# MAIN.net
KiCad netlist of a schematic drawn in Altium Designer
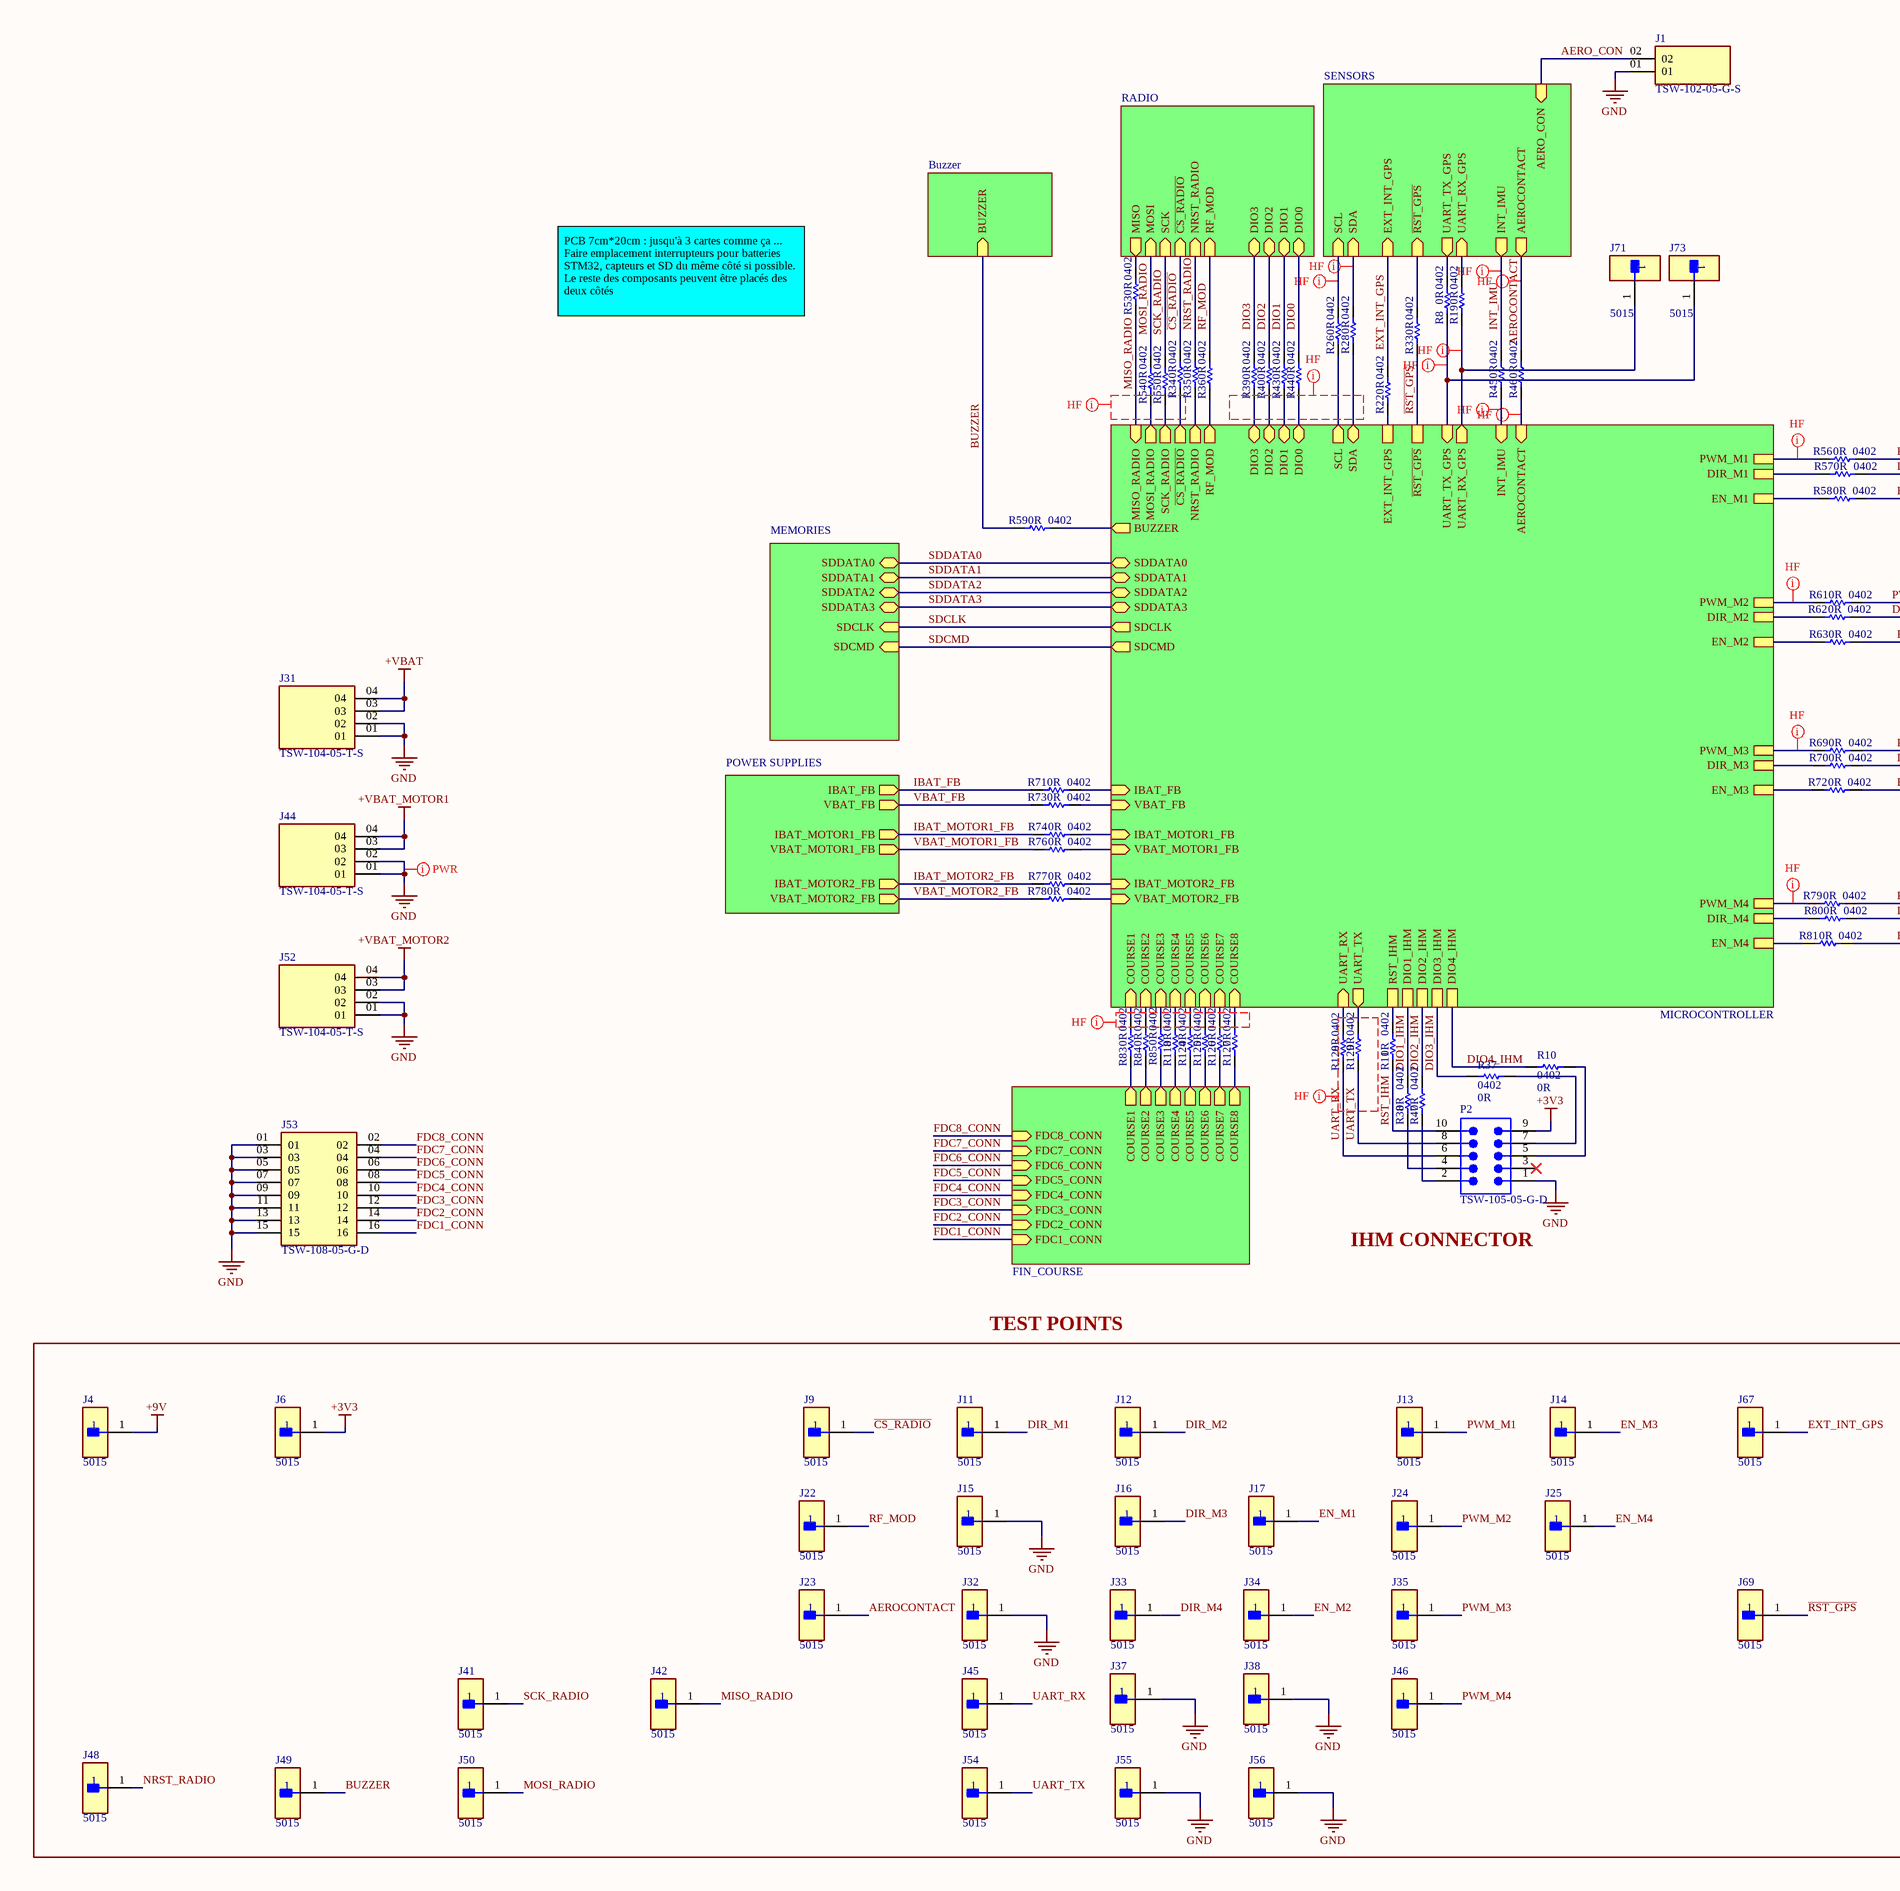
[diagram p0: MAIN.SchDoc, left]
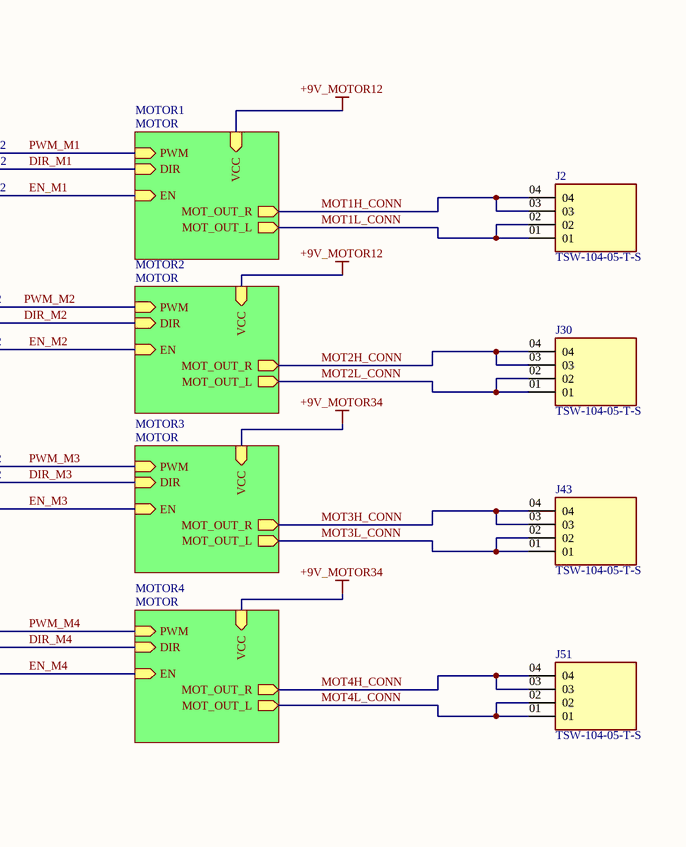
[diagram p1: MAIN.SchDoc, right]

(export (version "E")
  (design (tool "Eeschema 10.0.6"))
  (components
    (comp (ref "J1")
      (value "TSW-102-05-G-S")
      (footprint "TSW-102-05-G-S:SAMTEC_TSW-102-05-G-S")
      (fields (field (name "MF") "{'manufacturer': u'Samtec Inc.'}"))
      (libsource (lib "*") (part "TSW-102-05-G-S"))
    )
    (comp (ref "J2")
      (value "TSW-104-05-T-S")
      (footprint "TSW-104-05-T-S:SAMTEC_TSW-104-05-T-S")
      (fields (field (name "MF") "{'manufacturer': u'Samtec'}"))
      (libsource (lib "") (part "TSW-104-05-T-S_1"))
    )
    (comp (ref "J4")
      (value "5015")
      (footprint "FP-5015-MFG")
      (description "PC TEST POINT MINIATURE")
      (fields
        (field (name "MANUFACTURER") "keystone")
        (field (name "OCTOPART") "https://octopart.com/5015-keystone-3822")
      )
      (libsource (lib "Altium Content Vault") (part "dd45045ce8184df9e99e12baf3f412c"))
    )
    (comp (ref "J6")
      (value "5015")
      (footprint "FP-5015-MFG")
      (description "PC TEST POINT MINIATURE")
      (fields
        (field (name "MANUFACTURER") "keystone")
        (field (name "OCTOPART") "https://octopart.com/5015-keystone-3822")
      )
      (libsource (lib "Altium Content Vault") (part "dd45045ce8184df9e99e12baf3f412c"))
    )
    (comp (ref "J9")
      (value "5015")
      (footprint "FP-5015-MFG")
      (description "PC TEST POINT MINIATURE")
      (fields
        (field (name "MANUFACTURER") "keystone")
        (field (name "OCTOPART") "https://octopart.com/5015-keystone-3822")
      )
      (libsource (lib "Altium Content Vault") (part "dd45045ce8184df9e99e12baf3f412c"))
    )
    (comp (ref "J11")
      (value "5015")
      (footprint "FP-5015-MFG")
      (description "PC TEST POINT MINIATURE")
      (fields
        (field (name "MANUFACTURER") "keystone")
        (field (name "OCTOPART") "https://octopart.com/5015-keystone-3822")
      )
      (libsource (lib "Altium Content Vault") (part "dd45045ce8184df9e99e12baf3f412c"))
    )
    (comp (ref "J12")
      (value "5015")
      (footprint "FP-5015-MFG")
      (description "PC TEST POINT MINIATURE")
      (fields
        (field (name "MANUFACTURER") "keystone")
        (field (name "OCTOPART") "https://octopart.com/5015-keystone-3822")
      )
      (libsource (lib "Altium Content Vault") (part "dd45045ce8184df9e99e12baf3f412c"))
    )
    (comp (ref "J13")
      (value "5015")
      (footprint "FP-5015-MFG")
      (description "PC TEST POINT MINIATURE")
      (fields
        (field (name "MANUFACTURER") "keystone")
        (field (name "OCTOPART") "https://octopart.com/5015-keystone-3822")
      )
      (libsource (lib "Altium Content Vault") (part "dd45045ce8184df9e99e12baf3f412c"))
    )
    (comp (ref "J14")
      (value "5015")
      (footprint "FP-5015-MFG")
      (description "PC TEST POINT MINIATURE")
      (fields
        (field (name "MANUFACTURER") "keystone")
        (field (name "OCTOPART") "https://octopart.com/5015-keystone-3822")
      )
      (libsource (lib "Altium Content Vault") (part "dd45045ce8184df9e99e12baf3f412c"))
    )
    (comp (ref "J15")
      (value "5015")
      (footprint "FP-5015-MFG")
      (description "PC TEST POINT MINIATURE")
      (fields
        (field (name "MANUFACTURER") "keystone")
        (field (name "OCTOPART") "https://octopart.com/5015-keystone-3822")
      )
      (libsource (lib "Altium Content Vault") (part "dd45045ce8184df9e99e12baf3f412c"))
    )
    (comp (ref "J16")
      (value "5015")
      (footprint "FP-5015-MFG")
      (description "PC TEST POINT MINIATURE")
      (fields
        (field (name "MANUFACTURER") "keystone")
        (field (name "OCTOPART") "https://octopart.com/5015-keystone-3822")
      )
      (libsource (lib "Altium Content Vault") (part "dd45045ce8184df9e99e12baf3f412c"))
    )
    (comp (ref "J17")
      (value "5015")
      (footprint "FP-5015-MFG")
      (description "PC TEST POINT MINIATURE")
      (fields
        (field (name "MANUFACTURER") "keystone")
        (field (name "OCTOPART") "https://octopart.com/5015-keystone-3822")
      )
      (libsource (lib "Altium Content Vault") (part "dd45045ce8184df9e99e12baf3f412c"))
    )
    (comp (ref "J22")
      (value "5015")
      (footprint "FP-5015-MFG")
      (description "PC TEST POINT MINIATURE")
      (fields
        (field (name "MANUFACTURER") "keystone")
        (field (name "OCTOPART") "https://octopart.com/5015-keystone-3822")
      )
      (libsource (lib "Altium Content Vault") (part "dd45045ce8184df9e99e12baf3f412c"))
    )
    (comp (ref "J23")
      (value "5015")
      (footprint "FP-5015-MFG")
      (description "PC TEST POINT MINIATURE")
      (fields
        (field (name "MANUFACTURER") "keystone")
        (field (name "OCTOPART") "https://octopart.com/5015-keystone-3822")
      )
      (libsource (lib "Altium Content Vault") (part "dd45045ce8184df9e99e12baf3f412c"))
    )
    (comp (ref "J24")
      (value "5015")
      (footprint "FP-5015-MFG")
      (description "PC TEST POINT MINIATURE")
      (fields
        (field (name "MANUFACTURER") "keystone")
        (field (name "OCTOPART") "https://octopart.com/5015-keystone-3822")
      )
      (libsource (lib "Altium Content Vault") (part "dd45045ce8184df9e99e12baf3f412c"))
    )
    (comp (ref "J25")
      (value "5015")
      (footprint "FP-5015-MFG")
      (description "PC TEST POINT MINIATURE")
      (fields
        (field (name "MANUFACTURER") "keystone")
        (field (name "OCTOPART") "https://octopart.com/5015-keystone-3822")
      )
      (libsource (lib "Altium Content Vault") (part "dd45045ce8184df9e99e12baf3f412c"))
    )
    (comp (ref "J30")
      (value "TSW-104-05-T-S")
      (footprint "TSW-104-05-T-S:SAMTEC_TSW-104-05-T-S")
      (fields (field (name "MF") "{'manufacturer': u'Samtec'}"))
      (libsource (lib "") (part "TSW-104-05-T-S_1"))
    )
    (comp (ref "J31")
      (value "TSW-104-05-T-S")
      (footprint "TSW-104-05-T-S:SAMTEC_TSW-104-05-T-S")
      (fields (field (name "MF") "{'manufacturer': u'Samtec'}"))
      (libsource (lib "*") (part "TSW-104-05-T-S"))
    )
    (comp (ref "J32")
      (value "5015")
      (footprint "FP-5015-MFG")
      (description "PC TEST POINT MINIATURE")
      (fields
        (field (name "MANUFACTURER") "keystone")
        (field (name "OCTOPART") "https://octopart.com/5015-keystone-3822")
      )
      (libsource (lib "Altium Content Vault") (part "dd45045ce8184df9e99e12baf3f412c"))
    )
    (comp (ref "J33")
      (value "5015")
      (footprint "FP-5015-MFG")
      (description "PC TEST POINT MINIATURE")
      (fields
        (field (name "MANUFACTURER") "keystone")
        (field (name "OCTOPART") "https://octopart.com/5015-keystone-3822")
      )
      (libsource (lib "Altium Content Vault") (part "dd45045ce8184df9e99e12baf3f412c"))
    )
    (comp (ref "J34")
      (value "5015")
      (footprint "FP-5015-MFG")
      (description "PC TEST POINT MINIATURE")
      (fields
        (field (name "MANUFACTURER") "keystone")
        (field (name "OCTOPART") "https://octopart.com/5015-keystone-3822")
      )
      (libsource (lib "Altium Content Vault") (part "dd45045ce8184df9e99e12baf3f412c"))
    )
    (comp (ref "J35")
      (value "5015")
      (footprint "FP-5015-MFG")
      (description "PC TEST POINT MINIATURE")
      (fields
        (field (name "MANUFACTURER") "keystone")
        (field (name "OCTOPART") "https://octopart.com/5015-keystone-3822")
      )
      (libsource (lib "Altium Content Vault") (part "dd45045ce8184df9e99e12baf3f412c"))
    )
    (comp (ref "J37")
      (value "5015")
      (footprint "FP-5015-MFG")
      (description "PC TEST POINT MINIATURE")
      (fields
        (field (name "MANUFACTURER") "keystone")
        (field (name "OCTOPART") "https://octopart.com/5015-keystone-3822")
      )
      (libsource (lib "Altium Content Vault") (part "dd45045ce8184df9e99e12baf3f412c"))
    )
    (comp (ref "J38")
      (value "5015")
      (footprint "FP-5015-MFG")
      (description "PC TEST POINT MINIATURE")
      (fields
        (field (name "MANUFACTURER") "keystone")
        (field (name "OCTOPART") "https://octopart.com/5015-keystone-3822")
      )
      (libsource (lib "Altium Content Vault") (part "dd45045ce8184df9e99e12baf3f412c"))
    )
    (comp (ref "J41")
      (value "5015")
      (footprint "FP-5015-MFG")
      (description "PC TEST POINT MINIATURE")
      (fields
        (field (name "MANUFACTURER") "keystone")
        (field (name "OCTOPART") "https://octopart.com/5015-keystone-3822")
      )
      (libsource (lib "Altium Content Vault") (part "dd45045ce8184df9e99e12baf3f412c"))
    )
    (comp (ref "J42")
      (value "5015")
      (footprint "FP-5015-MFG")
      (description "PC TEST POINT MINIATURE")
      (fields
        (field (name "MANUFACTURER") "keystone")
        (field (name "OCTOPART") "https://octopart.com/5015-keystone-3822")
      )
      (libsource (lib "Altium Content Vault") (part "dd45045ce8184df9e99e12baf3f412c"))
    )
    (comp (ref "J43")
      (value "TSW-104-05-T-S")
      (footprint "TSW-104-05-T-S:SAMTEC_TSW-104-05-T-S")
      (fields (field (name "MF") "{'manufacturer': u'Samtec'}"))
      (libsource (lib "") (part "TSW-104-05-T-S_1"))
    )
    (comp (ref "J44")
      (value "TSW-104-05-T-S")
      (footprint "TSW-104-05-T-S:SAMTEC_TSW-104-05-T-S")
      (fields (field (name "MF") "{'manufacturer': u'Samtec'}"))
      (libsource (lib "*") (part "TSW-104-05-T-S"))
    )
    (comp (ref "J45")
      (value "5015")
      (footprint "FP-5015-MFG")
      (description "PC TEST POINT MINIATURE")
      (fields
        (field (name "MANUFACTURER") "keystone")
        (field (name "OCTOPART") "https://octopart.com/5015-keystone-3822")
      )
      (libsource (lib "Altium Content Vault") (part "dd45045ce8184df9e99e12baf3f412c"))
    )
    (comp (ref "J46")
      (value "5015")
      (footprint "FP-5015-MFG")
      (description "PC TEST POINT MINIATURE")
      (fields
        (field (name "MANUFACTURER") "keystone")
        (field (name "OCTOPART") "https://octopart.com/5015-keystone-3822")
      )
      (libsource (lib "Altium Content Vault") (part "dd45045ce8184df9e99e12baf3f412c"))
    )
    (comp (ref "J48")
      (value "5015")
      (footprint "FP-5015-MFG")
      (description "PC TEST POINT MINIATURE")
      (fields
        (field (name "MANUFACTURER") "keystone")
        (field (name "OCTOPART") "https://octopart.com/5015-keystone-3822")
      )
      (libsource (lib "Altium Content Vault") (part "dd45045ce8184df9e99e12baf3f412c"))
    )
    (comp (ref "J49")
      (value "5015")
      (footprint "FP-5015-MFG")
      (description "PC TEST POINT MINIATURE")
      (fields
        (field (name "MANUFACTURER") "keystone")
        (field (name "OCTOPART") "https://octopart.com/5015-keystone-3822")
      )
      (libsource (lib "Altium Content Vault") (part "dd45045ce8184df9e99e12baf3f412c"))
    )
    (comp (ref "J50")
      (value "5015")
      (footprint "FP-5015-MFG")
      (description "PC TEST POINT MINIATURE")
      (fields
        (field (name "MANUFACTURER") "keystone")
        (field (name "OCTOPART") "https://octopart.com/5015-keystone-3822")
      )
      (libsource (lib "Altium Content Vault") (part "dd45045ce8184df9e99e12baf3f412c"))
    )
    (comp (ref "J51")
      (value "TSW-104-05-T-S")
      (footprint "TSW-104-05-T-S:SAMTEC_TSW-104-05-T-S")
      (fields (field (name "MF") "{'manufacturer': u'Samtec'}"))
      (libsource (lib "") (part "TSW-104-05-T-S_1"))
    )
    (comp (ref "J52")
      (value "TSW-104-05-T-S")
      (footprint "TSW-104-05-T-S:SAMTEC_TSW-104-05-T-S")
      (fields (field (name "MF") "{'manufacturer': u'Samtec'}"))
      (libsource (lib "*") (part "TSW-104-05-T-S"))
    )
    (comp (ref "J53")
      (value "TSW-108-05-G-D")
      (footprint "TSW-108-05-G-D:SAMTEC_TSW-108-05-G-D")
      (fields (field (name "MF") "{'manufacturer': u'Samtec'}"))
      (libsource (lib "*") (part "TSW-108-05-G-D"))
    )
    (comp (ref "J54")
      (value "5015")
      (footprint "FP-5015-MFG")
      (description "PC TEST POINT MINIATURE")
      (fields
        (field (name "MANUFACTURER") "keystone")
        (field (name "OCTOPART") "https://octopart.com/5015-keystone-3822")
      )
      (libsource (lib "Altium Content Vault") (part "dd45045ce8184df9e99e12baf3f412c"))
    )
    (comp (ref "J55")
      (value "5015")
      (footprint "FP-5015-MFG")
      (description "PC TEST POINT MINIATURE")
      (fields
        (field (name "MANUFACTURER") "keystone")
        (field (name "OCTOPART") "https://octopart.com/5015-keystone-3822")
      )
      (libsource (lib "Altium Content Vault") (part "dd45045ce8184df9e99e12baf3f412c"))
    )
    (comp (ref "J56")
      (value "5015")
      (footprint "FP-5015-MFG")
      (description "PC TEST POINT MINIATURE")
      (fields
        (field (name "MANUFACTURER") "keystone")
        (field (name "OCTOPART") "https://octopart.com/5015-keystone-3822")
      )
      (libsource (lib "Altium Content Vault") (part "dd45045ce8184df9e99e12baf3f412c"))
    )
    (comp (ref "J67")
      (value "5015")
      (footprint "FP-5015-MFG")
      (description "PC TEST POINT MINIATURE")
      (fields
        (field (name "MANUFACTURER") "keystone")
        (field (name "OCTOPART") "https://octopart.com/5015-keystone-3822")
      )
      (libsource (lib "Altium Content Vault") (part "dd45045ce8184df9e99e12baf3f412c"))
    )
    (comp (ref "J69")
      (value "5015")
      (footprint "FP-5015-MFG")
      (description "PC TEST POINT MINIATURE")
      (fields
        (field (name "MANUFACTURER") "keystone")
        (field (name "OCTOPART") "https://octopart.com/5015-keystone-3822")
      )
      (libsource (lib "Altium Content Vault") (part "dd45045ce8184df9e99e12baf3f412c"))
    )
    (comp (ref "J71")
      (value "5015")
      (footprint "FP-5015-MFG")
      (description "PC TEST POINT MINIATURE")
      (fields
        (field (name "MANUFACTURER") "keystone")
        (field (name "OCTOPART") "https://octopart.com/5015-keystone-3822")
      )
      (libsource (lib "") (part "dd45045ce8184df9e99e12baf3f412c_1"))
    )
    (comp (ref "J73")
      (value "5015")
      (footprint "FP-5015-MFG")
      (description "PC TEST POINT MINIATURE")
      (fields
        (field (name "MANUFACTURER") "keystone")
        (field (name "OCTOPART") "https://octopart.com/5015-keystone-3822")
      )
      (libsource (lib "") (part "dd45045ce8184df9e99e12baf3f412c_1"))
    )
    (comp (ref "P2")
      (value "TSW-105-05-G-D")
      (footprint "SMTC-TSW-105-05-X-D")
      (description "0.025\" SQ Post Header, Through-hole, Vertical, -55 to 125 degC, 2.54 mm Pitch, 10-Pin, Male, RoHS")
      (fields (field (name "MANUFACTURER") "Samtec"))
      (libsource (lib "Altium Content Vault") (part "SMTC-TSW-105-X-X-D-X"))
    )
    (comp (ref "R8")
      (value "CRCW04020000Z0EDHP")
      (footprint "RESC1005X40X25ML05T10")
      (fields
        (field (name "MANUFACTURER") "Vishay Dale")
        (field (name "CASE CODE (IMPERIAL)") "0402")
        (field (name "RESISTANCE") "0R")
      )
      (libsource (lib "Altium Content Vault") (part "RES"))
    )
    (comp (ref "R10")
      (value "CRCW04020000Z0EDHP")
      (footprint "RESC1005X40X25ML05T10")
      (fields
        (field (name "MANUFACTURER") "Vishay Dale")
        (field (name "CASE CODE (IMPERIAL)") "0402")
        (field (name "RESISTANCE") "0R")
      )
      (libsource (lib "Altium Content Vault") (part "RES"))
    )
    (comp (ref "R11")
      (value "CRCW04020000Z0EDHP")
      (footprint "RESC1005X40X25ML05T10")
      (fields
        (field (name "MANUFACTURER") "Vishay Dale")
        (field (name "CASE CODE (IMPERIAL)") "0402")
        (field (name "RESISTANCE") "0R")
      )
      (libsource (lib "Altium Content Vault") (part "RES"))
    )
    (comp (ref "R19")
      (value "CRCW04020000Z0EDHP")
      (footprint "RESC1005X40X25ML05T10")
      (fields
        (field (name "MANUFACTURER") "Vishay Dale")
        (field (name "CASE CODE (IMPERIAL)") "0402")
        (field (name "RESISTANCE") "0R")
      )
      (libsource (lib "Altium Content Vault") (part "RES"))
    )
    (comp (ref "R22")
      (value "CRCW04020000Z0EDHP")
      (footprint "RESC1005X40X25ML05T10")
      (fields
        (field (name "MANUFACTURER") "Vishay Dale")
        (field (name "CASE CODE (IMPERIAL)") "0402")
        (field (name "RESISTANCE") "0R")
      )
      (libsource (lib "Altium Content Vault") (part "RES"))
    )
    (comp (ref "R26")
      (value "CRCW04020000Z0EDHP")
      (footprint "RESC1005X40X25ML05T10")
      (fields
        (field (name "MANUFACTURER") "Vishay Dale")
        (field (name "CASE CODE (IMPERIAL)") "0402")
        (field (name "RESISTANCE") "0R")
      )
      (libsource (lib "Altium Content Vault") (part "RES"))
    )
    (comp (ref "R28")
      (value "CRCW04020000Z0EDHP")
      (footprint "RESC1005X40X25ML05T10")
      (fields
        (field (name "MANUFACTURER") "Vishay Dale")
        (field (name "CASE CODE (IMPERIAL)") "0402")
        (field (name "RESISTANCE") "0R")
      )
      (libsource (lib "Altium Content Vault") (part "RES"))
    )
    (comp (ref "R33")
      (value "CRCW04020000Z0EDHP")
      (footprint "RESC1005X40X25ML05T10")
      (fields
        (field (name "MANUFACTURER") "Vishay Dale")
        (field (name "CASE CODE (IMPERIAL)") "0402")
        (field (name "RESISTANCE") "0R")
      )
      (libsource (lib "Altium Content Vault") (part "RES"))
    )
    (comp (ref "R34")
      (value "CRCW04020000Z0EDHP")
      (footprint "RESC1005X40X25ML05T10")
      (fields
        (field (name "MANUFACTURER") "Vishay Dale")
        (field (name "CASE CODE (IMPERIAL)") "0402")
        (field (name "RESISTANCE") "0R")
      )
      (libsource (lib "Altium Content Vault") (part "RES"))
    )
    (comp (ref "R35")
      (value "CRCW04020000Z0EDHP")
      (footprint "RESC1005X40X25ML05T10")
      (fields
        (field (name "MANUFACTURER") "Vishay Dale")
        (field (name "CASE CODE (IMPERIAL)") "0402")
        (field (name "RESISTANCE") "0R")
      )
      (libsource (lib "Altium Content Vault") (part "RES"))
    )
    (comp (ref "R36")
      (value "CRCW04020000Z0EDHP")
      (footprint "RESC1005X40X25ML05T10")
      (fields
        (field (name "MANUFACTURER") "Vishay Dale")
        (field (name "CASE CODE (IMPERIAL)") "0402")
        (field (name "RESISTANCE") "0R")
      )
      (libsource (lib "Altium Content Vault") (part "RES"))
    )
    (comp (ref "R37")
      (value "CRCW04020000Z0EDHP")
      (footprint "RESC1005X40X25ML05T10")
      (fields
        (field (name "MANUFACTURER") "Vishay Dale")
        (field (name "CASE CODE (IMPERIAL)") "0402")
        (field (name "RESISTANCE") "0R")
      )
      (libsource (lib "Altium Content Vault") (part "RES"))
    )
    (comp (ref "R38")
      (value "CRCW04020000Z0EDHP")
      (footprint "RESC1005X40X25ML05T10")
      (fields
        (field (name "MANUFACTURER") "Vishay Dale")
        (field (name "CASE CODE (IMPERIAL)") "0402")
        (field (name "RESISTANCE") "0R")
      )
      (libsource (lib "Altium Content Vault") (part "RES"))
    )
    (comp (ref "R39")
      (value "CRCW04020000Z0EDHP")
      (footprint "RESC1005X40X25ML05T10")
      (fields
        (field (name "MANUFACTURER") "Vishay Dale")
        (field (name "CASE CODE (IMPERIAL)") "0402")
        (field (name "RESISTANCE") "0R")
      )
      (libsource (lib "Altium Content Vault") (part "RES"))
    )
    (comp (ref "R40")
      (value "CRCW04020000Z0EDHP")
      (footprint "RESC1005X40X25ML05T10")
      (fields
        (field (name "MANUFACTURER") "Vishay Dale")
        (field (name "CASE CODE (IMPERIAL)") "0402")
        (field (name "RESISTANCE") "0R")
      )
      (libsource (lib "Altium Content Vault") (part "RES"))
    )
    (comp (ref "R43")
      (value "CRCW04020000Z0EDHP")
      (footprint "RESC1005X40X25ML05T10")
      (fields
        (field (name "MANUFACTURER") "Vishay Dale")
        (field (name "CASE CODE (IMPERIAL)") "0402")
        (field (name "RESISTANCE") "0R")
      )
      (libsource (lib "Altium Content Vault") (part "RES"))
    )
    (comp (ref "R44")
      (value "CRCW04020000Z0EDHP")
      (footprint "RESC1005X40X25ML05T10")
      (fields
        (field (name "MANUFACTURER") "Vishay Dale")
        (field (name "CASE CODE (IMPERIAL)") "0402")
        (field (name "RESISTANCE") "0R")
      )
      (libsource (lib "Altium Content Vault") (part "RES"))
    )
    (comp (ref "R45")
      (value "CRCW04020000Z0EDHP")
      (footprint "RESC1005X40X25ML05T10")
      (fields
        (field (name "MANUFACTURER") "Vishay Dale")
        (field (name "CASE CODE (IMPERIAL)") "0402")
        (field (name "RESISTANCE") "0R")
      )
      (libsource (lib "Altium Content Vault") (part "RES"))
    )
    (comp (ref "R46")
      (value "CRCW04020000Z0EDHP")
      (footprint "RESC1005X40X25ML05T10")
      (fields
        (field (name "MANUFACTURER") "Vishay Dale")
        (field (name "CASE CODE (IMPERIAL)") "0402")
        (field (name "RESISTANCE") "0R")
      )
      (libsource (lib "Altium Content Vault") (part "RES"))
    )
    (comp (ref "R47")
      (value "CRCW04020000Z0EDHP")
      (footprint "RESC1005X40X25ML05T10")
      (fields
        (field (name "MANUFACTURER") "Vishay Dale")
        (field (name "CASE CODE (IMPERIAL)") "0402")
        (field (name "RESISTANCE") "0R")
      )
      (libsource (lib "Altium Content Vault") (part "RES"))
    )
    (comp (ref "R53")
      (value "CRCW04020000Z0EDHP")
      (footprint "RESC1005X40X25ML05T10")
      (fields
        (field (name "MANUFACTURER") "Vishay Dale")
        (field (name "CASE CODE (IMPERIAL)") "0402")
        (field (name "RESISTANCE") "0R")
      )
      (libsource (lib "Altium Content Vault") (part "RES"))
    )
    (comp (ref "R54")
      (value "CRCW04020000Z0EDHP")
      (footprint "RESC1005X40X25ML05T10")
      (fields
        (field (name "MANUFACTURER") "Vishay Dale")
        (field (name "CASE CODE (IMPERIAL)") "0402")
        (field (name "RESISTANCE") "0R")
      )
      (libsource (lib "Altium Content Vault") (part "RES"))
    )
    (comp (ref "R55")
      (value "CRCW04020000Z0EDHP")
      (footprint "RESC1005X40X25ML05T10")
      (fields
        (field (name "MANUFACTURER") "Vishay Dale")
        (field (name "CASE CODE (IMPERIAL)") "0402")
        (field (name "RESISTANCE") "0R")
      )
      (libsource (lib "Altium Content Vault") (part "RES"))
    )
    (comp (ref "R56")
      (value "CRCW04020000Z0EDHP")
      (footprint "RESC1005X40X25ML05T10")
      (fields
        (field (name "MANUFACTURER") "Vishay Dale")
        (field (name "CASE CODE (IMPERIAL)") "0402")
        (field (name "RESISTANCE") "0R")
      )
      (libsource (lib "Altium Content Vault") (part "RES"))
    )
    (comp (ref "R57")
      (value "CRCW04020000Z0EDHP")
      (footprint "RESC1005X40X25ML05T10")
      (fields
        (field (name "MANUFACTURER") "Vishay Dale")
        (field (name "CASE CODE (IMPERIAL)") "0402")
        (field (name "RESISTANCE") "0R")
      )
      (libsource (lib "Altium Content Vault") (part "RES"))
    )
    (comp (ref "R58")
      (value "CRCW04020000Z0EDHP")
      (footprint "RESC1005X40X25ML05T10")
      (fields
        (field (name "MANUFACTURER") "Vishay Dale")
        (field (name "CASE CODE (IMPERIAL)") "0402")
        (field (name "RESISTANCE") "0R")
      )
      (libsource (lib "Altium Content Vault") (part "RES"))
    )
    (comp (ref "R59")
      (value "CRCW04020000Z0EDHP")
      (footprint "RESC1005X40X25ML05T10")
      (fields
        (field (name "MANUFACTURER") "Vishay Dale")
        (field (name "CASE CODE (IMPERIAL)") "0402")
        (field (name "RESISTANCE") "0R")
      )
      (libsource (lib "Altium Content Vault") (part "RES"))
    )
    (comp (ref "R61")
      (value "CRCW04020000Z0EDHP")
      (footprint "RESC1005X40X25ML05T10")
      (fields
        (field (name "MANUFACTURER") "Vishay Dale")
        (field (name "CASE CODE (IMPERIAL)") "0402")
        (field (name "RESISTANCE") "0R")
      )
      (libsource (lib "Altium Content Vault") (part "RES"))
    )
    (comp (ref "R62")
      (value "CRCW04020000Z0EDHP")
      (footprint "RESC1005X40X25ML05T10")
      (fields
        (field (name "MANUFACTURER") "Vishay Dale")
        (field (name "CASE CODE (IMPERIAL)") "0402")
        (field (name "RESISTANCE") "0R")
      )
      (libsource (lib "Altium Content Vault") (part "RES"))
    )
    (comp (ref "R63")
      (value "CRCW04020000Z0EDHP")
      (footprint "RESC1005X40X25ML05T10")
      (fields
        (field (name "MANUFACTURER") "Vishay Dale")
        (field (name "CASE CODE (IMPERIAL)") "0402")
        (field (name "RESISTANCE") "0R")
      )
      (libsource (lib "Altium Content Vault") (part "RES"))
    )
    (comp (ref "R69")
      (value "CRCW04020000Z0EDHP")
      (footprint "RESC1005X40X25ML05T10")
      (fields
        (field (name "MANUFACTURER") "Vishay Dale")
        (field (name "CASE CODE (IMPERIAL)") "0402")
        (field (name "RESISTANCE") "0R")
      )
      (libsource (lib "Altium Content Vault") (part "RES"))
    )
    (comp (ref "R70")
      (value "CRCW04020000Z0EDHP")
      (footprint "RESC1005X40X25ML05T10")
      (fields
        (field (name "MANUFACTURER") "Vishay Dale")
        (field (name "CASE CODE (IMPERIAL)") "0402")
        (field (name "RESISTANCE") "0R")
      )
      (libsource (lib "Altium Content Vault") (part "RES"))
    )
    (comp (ref "R71")
      (value "CRCW04020000Z0EDHP")
      (footprint "RESC1005X40X25ML05T10")
      (fields
        (field (name "MANUFACTURER") "Vishay Dale")
        (field (name "CASE CODE (IMPERIAL)") "0402")
        (field (name "RESISTANCE") "0R")
      )
      (libsource (lib "Altium Content Vault") (part "RES"))
    )
    (comp (ref "R72")
      (value "CRCW04020000Z0EDHP")
      (footprint "RESC1005X40X25ML05T10")
      (fields
        (field (name "MANUFACTURER") "Vishay Dale")
        (field (name "CASE CODE (IMPERIAL)") "0402")
        (field (name "RESISTANCE") "0R")
      )
      (libsource (lib "Altium Content Vault") (part "RES"))
    )
    (comp (ref "R73")
      (value "CRCW04020000Z0EDHP")
      (footprint "RESC1005X40X25ML05T10")
      (fields
        (field (name "MANUFACTURER") "Vishay Dale")
        (field (name "CASE CODE (IMPERIAL)") "0402")
        (field (name "RESISTANCE") "0R")
      )
      (libsource (lib "Altium Content Vault") (part "RES"))
    )
    (comp (ref "R74")
      (value "CRCW04020000Z0EDHP")
      (footprint "RESC1005X40X25ML05T10")
      (fields
        (field (name "MANUFACTURER") "Vishay Dale")
        (field (name "CASE CODE (IMPERIAL)") "0402")
        (field (name "RESISTANCE") "0R")
      )
      (libsource (lib "Altium Content Vault") (part "RES"))
    )
    (comp (ref "R76")
      (value "CRCW04020000Z0EDHP")
      (footprint "RESC1005X40X25ML05T10")
      (fields
        (field (name "MANUFACTURER") "Vishay Dale")
        (field (name "CASE CODE (IMPERIAL)") "0402")
        (field (name "RESISTANCE") "0R")
      )
      (libsource (lib "Altium Content Vault") (part "RES"))
    )
    (comp (ref "R77")
      (value "CRCW04020000Z0EDHP")
      (footprint "RESC1005X40X25ML05T10")
      (fields
        (field (name "MANUFACTURER") "Vishay Dale")
        (field (name "CASE CODE (IMPERIAL)") "0402")
        (field (name "RESISTANCE") "0R")
      )
      (libsource (lib "Altium Content Vault") (part "RES"))
    )
    (comp (ref "R78")
      (value "CRCW04020000Z0EDHP")
      (footprint "RESC1005X40X25ML05T10")
      (fields
        (field (name "MANUFACTURER") "Vishay Dale")
        (field (name "CASE CODE (IMPERIAL)") "0402")
        (field (name "RESISTANCE") "0R")
      )
      (libsource (lib "Altium Content Vault") (part "RES"))
    )
    (comp (ref "R79")
      (value "CRCW04020000Z0EDHP")
      (footprint "RESC1005X40X25ML05T10")
      (fields
        (field (name "MANUFACTURER") "Vishay Dale")
        (field (name "CASE CODE (IMPERIAL)") "0402")
        (field (name "RESISTANCE") "0R")
      )
      (libsource (lib "Altium Content Vault") (part "RES"))
    )
    (comp (ref "R80")
      (value "CRCW04020000Z0EDHP")
      (footprint "RESC1005X40X25ML05T10")
      (fields
        (field (name "MANUFACTURER") "Vishay Dale")
        (field (name "CASE CODE (IMPERIAL)") "0402")
        (field (name "RESISTANCE") "0R")
      )
      (libsource (lib "Altium Content Vault") (part "RES"))
    )
    (comp (ref "R81")
      (value "CRCW04020000Z0EDHP")
      (footprint "RESC1005X40X25ML05T10")
      (fields
        (field (name "MANUFACTURER") "Vishay Dale")
        (field (name "CASE CODE (IMPERIAL)") "0402")
        (field (name "RESISTANCE") "0R")
      )
      (libsource (lib "Altium Content Vault") (part "RES"))
    )
    (comp (ref "R83")
      (value "CRCW04020000Z0EDHP")
      (footprint "RESC1005X40X25ML05T10")
      (fields
        (field (name "MANUFACTURER") "Vishay Dale")
        (field (name "CASE CODE (IMPERIAL)") "0402")
        (field (name "RESISTANCE") "0R")
      )
      (libsource (lib "Altium Content Vault") (part "RES"))
    )
    (comp (ref "R84")
      (value "CRCW04020000Z0EDHP")
      (footprint "RESC1005X40X25ML05T10")
      (fields
        (field (name "MANUFACTURER") "Vishay Dale")
        (field (name "CASE CODE (IMPERIAL)") "0402")
        (field (name "RESISTANCE") "0R")
      )
      (libsource (lib "Altium Content Vault") (part "RES"))
    )
    (comp (ref "R85")
      (value "CRCW04020000Z0EDHP")
      (footprint "RESC1005X40X25ML05T10")
      (fields
        (field (name "MANUFACTURER") "Vishay Dale")
        (field (name "CASE CODE (IMPERIAL)") "0402")
        (field (name "RESISTANCE") "0R")
      )
      (libsource (lib "Altium Content Vault") (part "RES"))
    )
    (comp (ref "R118")
      (value "CRCW04020000Z0EDHP")
      (footprint "RESC1005X40X25ML05T10")
      (fields
        (field (name "MANUFACTURER") "Vishay Dale")
        (field (name "CASE CODE (IMPERIAL)") "0402")
        (field (name "RESISTANCE") "0R")
      )
      (libsource (lib "Altium Content Vault") (part "RES"))
    )
    (comp (ref "R124")
      (value "CRCW04020000Z0EDHP")
      (footprint "RESC1005X40X25ML05T10")
      (fields
        (field (name "MANUFACTURER") "Vishay Dale")
        (field (name "CASE CODE (IMPERIAL)") "0402")
        (field (name "RESISTANCE") "0R")
      )
      (libsource (lib "Altium Content Vault") (part "RES"))
    )
    (comp (ref "R125")
      (value "CRCW04020000Z0EDHP")
      (footprint "RESC1005X40X25ML05T10")
      (fields
        (field (name "MANUFACTURER") "Vishay Dale")
        (field (name "CASE CODE (IMPERIAL)") "0402")
        (field (name "RESISTANCE") "0R")
      )
      (libsource (lib "Altium Content Vault") (part "RES"))
    )
    (comp (ref "R126")
      (value "CRCW04020000Z0EDHP")
      (footprint "RESC1005X40X25ML05T10")
      (fields
        (field (name "MANUFACTURER") "Vishay Dale")
        (field (name "CASE CODE (IMPERIAL)") "0402")
        (field (name "RESISTANCE") "0R")
      )
      (libsource (lib "Altium Content Vault") (part "RES"))
    )
    (comp (ref "R127")
      (value "CRCW04020000Z0EDHP")
      (footprint "RESC1005X40X25ML05T10")
      (fields
        (field (name "MANUFACTURER") "Vishay Dale")
        (field (name "CASE CODE (IMPERIAL)") "0402")
        (field (name "RESISTANCE") "0R")
      )
      (libsource (lib "Altium Content Vault") (part "RES"))
    )
    (comp (ref "R128")
      (value "CRCW04020000Z0EDHP")
      (footprint "RESC1005X40X25ML05T10")
      (fields
        (field (name "MANUFACTURER") "Vishay Dale")
        (field (name "CASE CODE (IMPERIAL)") "0402")
        (field (name "RESISTANCE") "0R")
      )
      (libsource (lib "Altium Content Vault") (part "RES"))
    )
    (comp (ref "R129")
      (value "CRCW04020000Z0EDHP")
      (footprint "RESC1005X40X25ML05T10")
      (fields
        (field (name "MANUFACTURER") "Vishay Dale")
        (field (name "CASE CODE (IMPERIAL)") "0402")
        (field (name "RESISTANCE") "0R")
      )
      (libsource (lib "Altium Content Vault") (part "RES"))
    )
  )
  (nets
    (net (code "1") (name "+3V3") (class "Default")
      (node (ref "J6") (pin "1") (pinfunction "1_1") (pintype "passive"))
      (node (ref "P2") (pin "9") (pinfunction "9_9") (pintype "passive"))
    )
    (net (code "2") (name "+9V") (class "Default")
      (node (ref "J4") (pin "1") (pinfunction "1_1") (pintype "passive"))
    )
    (net (code "5") (name "+VBAT") (class "Default")
      (node (ref "J31") (pin "03") (pinfunction "03_03") (pintype "passive"))
      (node (ref "J31") (pin "04") (pinfunction "04_04") (pintype "passive"))
    )
    (net (code "6") (name "+VBAT_MOTOR1") (class "Default")
      (node (ref "J44") (pin "03") (pinfunction "03_03") (pintype "passive"))
      (node (ref "J44") (pin "04") (pinfunction "04_04") (pintype "passive"))
    )
    (net (code "7") (name "+VBAT_MOTOR2") (class "Default")
      (node (ref "J52") (pin "03") (pinfunction "03_03") (pintype "passive"))
      (node (ref "J52") (pin "04") (pinfunction "04_04") (pintype "passive"))
    )
    (net (code "8") (name "/AEROCONTACT") (class "Default")
      (node (ref "J23") (pin "1") (pinfunction "1_1") (pintype "passive"))
      (node (ref "R46") (pin "2") (pinfunction "2_2") (pintype "passive"))
    )
    (net (code "9") (name "/AEROCONTACT_1") (class "Default")
      (node (ref "R46") (pin "1") (pinfunction "1_1") (pintype "passive"))
    )
    (net (code "10") (name "/AERO_CON") (class "Default")
      (node (ref "J1") (pin "02") (pinfunction "02_02") (pintype "passive"))
    )
    (net (code "11") (name "/BUZZER") (class "Default")
      (node (ref "J49") (pin "1") (pinfunction "1_1") (pintype "passive"))
      (node (ref "R59") (pin "2") (pinfunction "2_2") (pintype "passive"))
    )
    (net (code "12") (name "/BUZZER_1") (class "Default")
      (node (ref "R59") (pin "1") (pinfunction "1_1") (pintype "passive"))
    )
    (net (code "13") (name "/COURSE1") (class "Default")
      (node (ref "R83") (pin "2") (pinfunction "2_2") (pintype "passive"))
    )
    (net (code "14") (name "/COURSE1_1") (class "Default")
      (node (ref "R83") (pin "1") (pinfunction "1_1") (pintype "passive"))
    )
    (net (code "15") (name "/COURSE2") (class "Default")
      (node (ref "R84") (pin "2") (pinfunction "2_2") (pintype "passive"))
    )
    (net (code "16") (name "/COURSE2_1") (class "Default")
      (node (ref "R84") (pin "1") (pinfunction "1_1") (pintype "passive"))
    )
    (net (code "17") (name "/COURSE3") (class "Default")
      (node (ref "R85") (pin "2") (pinfunction "2_2") (pintype "passive"))
    )
    (net (code "18") (name "/COURSE3_1") (class "Default")
      (node (ref "R85") (pin "1") (pinfunction "1_1") (pintype "passive"))
    )
    (net (code "19") (name "/COURSE4") (class "Default")
      (node (ref "R118") (pin "2") (pinfunction "2_2") (pintype "passive"))
    )
    (net (code "20") (name "/COURSE4_1") (class "Default")
      (node (ref "R118") (pin "1") (pinfunction "1_1") (pintype "passive"))
    )
    (net (code "21") (name "/COURSE5") (class "Default")
      (node (ref "R124") (pin "2") (pinfunction "2_2") (pintype "passive"))
    )
    (net (code "22") (name "/COURSE5_1") (class "Default")
      (node (ref "R124") (pin "1") (pinfunction "1_1") (pintype "passive"))
    )
    (net (code "23") (name "/COURSE6") (class "Default")
      (node (ref "R125") (pin "1") (pinfunction "1_1") (pintype "passive"))
    )
    (net (code "24") (name "/COURSE6_1") (class "Default")
      (node (ref "R125") (pin "2") (pinfunction "2_2") (pintype "passive"))
    )
    (net (code "25") (name "/COURSE7") (class "Default")
      (node (ref "R126") (pin "1") (pinfunction "1_1") (pintype "passive"))
    )
    (net (code "26") (name "/COURSE7_1") (class "Default")
      (node (ref "R126") (pin "2") (pinfunction "2_2") (pintype "passive"))
    )
    (net (code "27") (name "/COURSE8") (class "Default")
      (node (ref "R127") (pin "1") (pinfunction "1_1") (pintype "passive"))
    )
    (net (code "28") (name "/COURSE8_1") (class "Default")
      (node (ref "R127") (pin "2") (pinfunction "2_2") (pintype "passive"))
    )
    (net (code "29") (name "/CS_RADIO") (class "Default")
      (node (ref "J9") (pin "1") (pinfunction "1_1") (pintype "passive"))
      (node (ref "R34") (pin "2") (pinfunction "2_2") (pintype "passive"))
    )
    (net (code "30") (name "/CS_RADIO_1") (class "Default")
      (node (ref "R34") (pin "1") (pinfunction "1_1") (pintype "passive"))
    )
    (net (code "31") (name "/DIO0") (class "Default")
      (node (ref "R44") (pin "2") (pinfunction "2_2") (pintype "passive"))
    )
    (net (code "32") (name "/DIO0_1") (class "Default")
      (node (ref "R44") (pin "1") (pinfunction "1_1") (pintype "passive"))
    )
    (net (code "33") (name "/DIO1") (class "Default")
      (node (ref "R43") (pin "2") (pinfunction "2_2") (pintype "passive"))
    )
    (net (code "34") (name "/DIO1_1") (class "Default")
      (node (ref "R43") (pin "1") (pinfunction "1_1") (pintype "passive"))
    )
    (net (code "35") (name "/DIO1_IHM") (class "Default")
      (node (ref "R38") (pin "2") (pinfunction "2_2") (pintype "passive"))
    )
    (net (code "36") (name "/DIO2") (class "Default")
      (node (ref "R40") (pin "2") (pinfunction "2_2") (pintype "passive"))
    )
    (net (code "37") (name "/DIO2_1") (class "Default")
      (node (ref "R40") (pin "1") (pinfunction "1_1") (pintype "passive"))
    )
    (net (code "38") (name "/DIO2_IHM") (class "Default")
      (node (ref "R47") (pin "2") (pinfunction "2_2") (pintype "passive"))
    )
    (net (code "39") (name "/DIO3") (class "Default")
      (node (ref "R39") (pin "2") (pinfunction "2_2") (pintype "passive"))
    )
    (net (code "40") (name "/DIO3_1") (class "Default")
      (node (ref "R39") (pin "1") (pinfunction "1_1") (pintype "passive"))
    )
    (net (code "41") (name "/DIO3_IHM") (class "Default")
      (node (ref "R37") (pin "2") (pinfunction "2_2") (pintype "passive"))
    )
    (net (code "42") (name "/DIO4_IHM") (class "Default")
      (node (ref "R10") (pin "2") (pinfunction "2_2") (pintype "passive"))
    )
    (net (code "43") (name "/DIR_M1") (class "Default")
      (node (ref "J11") (pin "1") (pinfunction "1_1") (pintype "passive"))
      (node (ref "R57") (pin "1") (pinfunction "1_1") (pintype "passive"))
    )
    (net (code "44") (name "/DIR_M1_1") (class "Default")
      (node (ref "R57") (pin "2") (pinfunction "2_2") (pintype "passive"))
    )
    (net (code "45") (name "/DIR_M2") (class "Default")
      (node (ref "J12") (pin "1") (pinfunction "1_1") (pintype "passive"))
      (node (ref "R62") (pin "1") (pinfunction "1_1") (pintype "passive"))
    )
    (net (code "46") (name "/DIR_M2_1") (class "Default")
      (node (ref "R62") (pin "2") (pinfunction "2_2") (pintype "passive"))
    )
    (net (code "47") (name "/DIR_M3") (class "Default")
      (node (ref "J16") (pin "1") (pinfunction "1_1") (pintype "passive"))
      (node (ref "R70") (pin "1") (pinfunction "1_1") (pintype "passive"))
    )
    (net (code "48") (name "/DIR_M3_1") (class "Default")
      (node (ref "R70") (pin "2") (pinfunction "2_2") (pintype "passive"))
    )
    (net (code "49") (name "/DIR_M4") (class "Default")
      (node (ref "J33") (pin "1") (pinfunction "1_1") (pintype "passive"))
      (node (ref "R80") (pin "1") (pinfunction "1_1") (pintype "passive"))
    )
    (net (code "50") (name "/DIR_M4_1") (class "Default")
      (node (ref "R80") (pin "2") (pinfunction "2_2") (pintype "passive"))
    )
    (net (code "51") (name "/EN_M1") (class "Default")
      (node (ref "J17") (pin "1") (pinfunction "1_1") (pintype "passive"))
      (node (ref "R58") (pin "1") (pinfunction "1_1") (pintype "passive"))
    )
    (net (code "52") (name "/EN_M1_1") (class "Default")
      (node (ref "R58") (pin "2") (pinfunction "2_2") (pintype "passive"))
    )
    (net (code "53") (name "/EN_M2") (class "Default")
      (node (ref "J34") (pin "1") (pinfunction "1_1") (pintype "passive"))
      (node (ref "R63") (pin "1") (pinfunction "1_1") (pintype "passive"))
    )
    (net (code "54") (name "/EN_M2_1") (class "Default")
      (node (ref "R63") (pin "2") (pinfunction "2_2") (pintype "passive"))
    )
    (net (code "55") (name "/EN_M3") (class "Default")
      (node (ref "J14") (pin "1") (pinfunction "1_1") (pintype "passive"))
      (node (ref "R72") (pin "1") (pinfunction "1_1") (pintype "passive"))
    )
    (net (code "56") (name "/EN_M3_1") (class "Default")
      (node (ref "R72") (pin "2") (pinfunction "2_2") (pintype "passive"))
    )
    (net (code "57") (name "/EN_M4") (class "Default")
      (node (ref "J25") (pin "1") (pinfunction "1_1") (pintype "passive"))
      (node (ref "R81") (pin "1") (pinfunction "1_1") (pintype "passive"))
    )
    (net (code "58") (name "/EN_M4_1") (class "Default")
      (node (ref "R81") (pin "2") (pinfunction "2_2") (pintype "passive"))
    )
    (net (code "59") (name "/EXT_INT_GPS") (class "Default")
      (node (ref "J67") (pin "1") (pinfunction "1_1") (pintype "passive"))
      (node (ref "R22") (pin "2") (pinfunction "2_2") (pintype "passive"))
    )
    (net (code "60") (name "/EXT_INT_GPS_1") (class "Default")
      (node (ref "R22") (pin "1") (pinfunction "1_1") (pintype "passive"))
    )
    (net (code "61") (name "/FDC1_CONN") (class "Default")
      (node (ref "J53") (pin "16") (pinfunction "16_16") (pintype "passive"))
    )
    (net (code "62") (name "/FDC2_CONN") (class "Default")
      (node (ref "J53") (pin "14") (pinfunction "14_14") (pintype "passive"))
    )
    (net (code "63") (name "/FDC3_CONN") (class "Default")
      (node (ref "J53") (pin "12") (pinfunction "12_12") (pintype "passive"))
    )
    (net (code "64") (name "/FDC4_CONN") (class "Default")
      (node (ref "J53") (pin "10") (pinfunction "10_10") (pintype "passive"))
    )
    (net (code "65") (name "/FDC5_CONN") (class "Default")
      (node (ref "J53") (pin "08") (pinfunction "08_08") (pintype "passive"))
    )
    (net (code "66") (name "/FDC6_CONN") (class "Default")
      (node (ref "J53") (pin "06") (pinfunction "06_06") (pintype "passive"))
    )
    (net (code "67") (name "/FDC7_CONN") (class "Default")
      (node (ref "J53") (pin "04") (pinfunction "04_04") (pintype "passive"))
    )
    (net (code "68") (name "/FDC8_CONN") (class "Default")
      (node (ref "J53") (pin "02") (pinfunction "02_02") (pintype "passive"))
    )
    (net (code "69") (name "/IBAT_FB") (class "Default")
      (node (ref "R71") (pin "2") (pinfunction "2_2") (pintype "passive"))
    )
    (net (code "70") (name "/IBAT_FB_1") (class "Default")
      (node (ref "R71") (pin "1") (pinfunction "1_1") (pintype "passive"))
    )
    (net (code "71") (name "/IBAT_MOTOR1_FB") (class "Default")
      (node (ref "R74") (pin "2") (pinfunction "2_2") (pintype "passive"))
    )
    (net (code "72") (name "/IBAT_MOTOR1_FB_1") (class "Default")
      (node (ref "R74") (pin "1") (pinfunction "1_1") (pintype "passive"))
    )
    (net (code "73") (name "/IBAT_MOTOR2_FB") (class "Default")
      (node (ref "R77") (pin "2") (pinfunction "2_2") (pintype "passive"))
    )
    (net (code "74") (name "/IBAT_MOTOR2_FB_1") (class "Default")
      (node (ref "R77") (pin "1") (pinfunction "1_1") (pintype "passive"))
    )
    (net (code "75") (name "/INT_IMU") (class "Default")
      (node (ref "R45") (pin "2") (pinfunction "2_2") (pintype "passive"))
    )
    (net (code "76") (name "/INT_IMU_1") (class "Default")
      (node (ref "R45") (pin "1") (pinfunction "1_1") (pintype "passive"))
    )
    (net (code "77") (name "/MISO") (class "Default")
      (node (ref "R53") (pin "2") (pinfunction "2_2") (pintype "passive"))
    )
    (net (code "78") (name "/MISO_RADIO") (class "Default")
      (node (ref "J42") (pin "1") (pinfunction "1_1") (pintype "passive"))
      (node (ref "R53") (pin "1") (pinfunction "1_1") (pintype "passive"))
    )
    (net (code "79") (name "/MOSI_RADIO") (class "Default")
      (node (ref "J50") (pin "1") (pinfunction "1_1") (pintype "passive"))
      (node (ref "R54") (pin "2") (pinfunction "2_2") (pintype "passive"))
    )
    (net (code "80") (name "/MOSI_RADIO_1") (class "Default")
      (node (ref "R54") (pin "1") (pinfunction "1_1") (pintype "passive"))
    )
    (net (code "81") (name "/MOT1H_CONN") (class "Default")
      (node (ref "J2") (pin "03") (pinfunction "03_03") (pintype "passive"))
      (node (ref "J2") (pin "04") (pinfunction "04_04") (pintype "passive"))
    )
    (net (code "82") (name "/MOT1L_CONN") (class "Default")
      (node (ref "J2") (pin "01") (pinfunction "01_01") (pintype "passive"))
      (node (ref "J2") (pin "02") (pinfunction "02_02") (pintype "passive"))
    )
    (net (code "83") (name "/MOT2H_CONN") (class "Default")
      (node (ref "J30") (pin "03") (pinfunction "03_03") (pintype "passive"))
      (node (ref "J30") (pin "04") (pinfunction "04_04") (pintype "passive"))
    )
    (net (code "84") (name "/MOT2L_CONN") (class "Default")
      (node (ref "J30") (pin "01") (pinfunction "01_01") (pintype "passive"))
      (node (ref "J30") (pin "02") (pinfunction "02_02") (pintype "passive"))
    )
    (net (code "85") (name "/MOT3H_CONN") (class "Default")
      (node (ref "J43") (pin "03") (pinfunction "03_03") (pintype "passive"))
      (node (ref "J43") (pin "04") (pinfunction "04_04") (pintype "passive"))
    )
    (net (code "86") (name "/MOT3L_CONN") (class "Default")
      (node (ref "J43") (pin "01") (pinfunction "01_01") (pintype "passive"))
      (node (ref "J43") (pin "02") (pinfunction "02_02") (pintype "passive"))
    )
    (net (code "87") (name "/MOT4H_CONN") (class "Default")
      (node (ref "J51") (pin "03") (pinfunction "03_03") (pintype "passive"))
      (node (ref "J51") (pin "04") (pinfunction "04_04") (pintype "passive"))
    )
    (net (code "88") (name "/MOT4L_CONN") (class "Default")
      (node (ref "J51") (pin "01") (pinfunction "01_01") (pintype "passive"))
      (node (ref "J51") (pin "02") (pinfunction "02_02") (pintype "passive"))
    )
    (net (code "89") (name "/NRST_RADIO") (class "Default")
      (node (ref "J48") (pin "1") (pinfunction "1_1") (pintype "passive"))
      (node (ref "R35") (pin "2") (pinfunction "2_2") (pintype "passive"))
    )
    (net (code "90") (name "/NRST_RADIO_1") (class "Default")
      (node (ref "R35") (pin "1") (pinfunction "1_1") (pintype "passive"))
    )
    (net (code "91") (name "/PWM_M1") (class "Default")
      (node (ref "J13") (pin "1") (pinfunction "1_1") (pintype "passive"))
      (node (ref "R56") (pin "1") (pinfunction "1_1") (pintype "passive"))
    )
    (net (code "92") (name "/PWM_M1_1") (class "Default")
      (node (ref "R56") (pin "2") (pinfunction "2_2") (pintype "passive"))
    )
    (net (code "93") (name "/PWM_M2") (class "Default")
      (node (ref "J24") (pin "1") (pinfunction "1_1") (pintype "passive"))
      (node (ref "R61") (pin "1") (pinfunction "1_1") (pintype "passive"))
    )
    (net (code "94") (name "/PWM_M2_1") (class "Default")
      (node (ref "R61") (pin "2") (pinfunction "2_2") (pintype "passive"))
    )
    (net (code "95") (name "/PWM_M3") (class "Default")
      (node (ref "J35") (pin "1") (pinfunction "1_1") (pintype "passive"))
      (node (ref "R69") (pin "1") (pinfunction "1_1") (pintype "passive"))
    )
    (net (code "96") (name "/PWM_M3_1") (class "Default")
      (node (ref "R69") (pin "2") (pinfunction "2_2") (pintype "passive"))
    )
    (net (code "97") (name "/PWM_M4") (class "Default")
      (node (ref "J46") (pin "1") (pinfunction "1_1") (pintype "passive"))
      (node (ref "R79") (pin "1") (pinfunction "1_1") (pintype "passive"))
    )
    (net (code "98") (name "/PWM_M4_1") (class "Default")
      (node (ref "R79") (pin "2") (pinfunction "2_2") (pintype "passive"))
    )
    (net (code "99") (name "/RF_MOD") (class "Default")
      (node (ref "J22") (pin "1") (pinfunction "1_1") (pintype "passive"))
      (node (ref "R36") (pin "2") (pinfunction "2_2") (pintype "passive"))
    )
    (net (code "100") (name "/RF_MOD_1") (class "Default")
      (node (ref "R36") (pin "1") (pinfunction "1_1") (pintype "passive"))
    )
    (net (code "101") (name "/RST_GPS") (class "Default")
      (node (ref "J69") (pin "1") (pinfunction "1_1") (pintype "passive"))
      (node (ref "R33") (pin "1") (pinfunction "1_1") (pintype "passive"))
    )
    (net (code "102") (name "/RST_GPS_1") (class "Default")
      (node (ref "R33") (pin "2") (pinfunction "2_2") (pintype "passive"))
    )
    (net (code "103") (name "/RST_IHM") (class "Default")
      (node (ref "P2") (pin "10") (pinfunction "10_10") (pintype "passive"))
      (node (ref "R11") (pin "1") (pinfunction "1_1") (pintype "passive"))
    )
    (net (code "104") (name "/RST_IHM_1") (class "Default")
      (node (ref "R11") (pin "2") (pinfunction "2_2") (pintype "passive"))
    )
    (net (code "105") (name "/SCK_RADIO") (class "Default")
      (node (ref "J41") (pin "1") (pinfunction "1_1") (pintype "passive"))
      (node (ref "R55") (pin "2") (pinfunction "2_2") (pintype "passive"))
    )
    (net (code "106") (name "/SCK_RADIO_1") (class "Default")
      (node (ref "R55") (pin "1") (pinfunction "1_1") (pintype "passive"))
    )
    (net (code "107") (name "/SCL") (class "Default")
      (node (ref "R26") (pin "1") (pinfunction "1_1") (pintype "passive"))
    )
    (net (code "108") (name "/SCL_1") (class "Default")
      (node (ref "R26") (pin "2") (pinfunction "2_2") (pintype "passive"))
    )
    (net (code "109") (name "/SDA") (class "Default")
      (node (ref "R28") (pin "1") (pinfunction "1_1") (pintype "passive"))
    )
    (net (code "110") (name "/SDA_1") (class "Default")
      (node (ref "R28") (pin "2") (pinfunction "2_2") (pintype "passive"))
    )
    (net (code "117") (name "/UART_RX") (class "Default")
      (node (ref "J45") (pin "1") (pinfunction "1_1") (pintype "passive"))
      (node (ref "P2") (pin "6") (pinfunction "6_6") (pintype "passive"))
      (node (ref "R128") (pin "1") (pinfunction "1_1") (pintype "passive"))
    )
    (net (code "118") (name "/UART_RX_1") (class "Default")
      (node (ref "R128") (pin "2") (pinfunction "2_2") (pintype "passive"))
    )
    (net (code "119") (name "/UART_RX_GPS") (class "Default")
      (node (ref "R19") (pin "2") (pinfunction "2_2") (pintype "passive"))
    )
    (net (code "120") (name "/UART_RX_GPS_1") (class "Default")
      (node (ref "J71") (pin "1") (pinfunction "1_1") (pintype "passive"))
      (node (ref "R19") (pin "1") (pinfunction "1_1") (pintype "passive"))
    )
    (net (code "121") (name "/UART_TX") (class "Default")
      (node (ref "J54") (pin "1") (pinfunction "1_1") (pintype "passive"))
      (node (ref "P2") (pin "8") (pinfunction "8_8") (pintype "passive"))
      (node (ref "R129") (pin "1") (pinfunction "1_1") (pintype "passive"))
    )
    (net (code "122") (name "/UART_TX_1") (class "Default")
      (node (ref "R129") (pin "2") (pinfunction "2_2") (pintype "passive"))
    )
    (net (code "123") (name "/UART_TX_GPS") (class "Default")
      (node (ref "R8") (pin "2") (pinfunction "2_2") (pintype "passive"))
    )
    (net (code "124") (name "/UART_TX_GPS_1") (class "Default")
      (node (ref "J73") (pin "1") (pinfunction "1_1") (pintype "passive"))
      (node (ref "R8") (pin "1") (pinfunction "1_1") (pintype "passive"))
    )
    (net (code "125") (name "/VBAT_FB") (class "Default")
      (node (ref "R73") (pin "2") (pinfunction "2_2") (pintype "passive"))
    )
    (net (code "126") (name "/VBAT_FB_1") (class "Default")
      (node (ref "R73") (pin "1") (pinfunction "1_1") (pintype "passive"))
    )
    (net (code "127") (name "/VBAT_MOTOR1_FB") (class "Default")
      (node (ref "R76") (pin "2") (pinfunction "2_2") (pintype "passive"))
    )
    (net (code "128") (name "/VBAT_MOTOR1_FB_1") (class "Default")
      (node (ref "R76") (pin "1") (pinfunction "1_1") (pintype "passive"))
    )
    (net (code "129") (name "/VBAT_MOTOR2_FB") (class "Default")
      (node (ref "R78") (pin "2") (pinfunction "2_2") (pintype "passive"))
    )
    (net (code "130") (name "/VBAT_MOTOR2_FB_1") (class "Default")
      (node (ref "R78") (pin "1") (pinfunction "1_1") (pintype "passive"))
    )
    (net (code "131") (name "GND") (class "Default")
      (node (ref "J1") (pin "01") (pinfunction "01_01") (pintype "passive"))
      (node (ref "J15") (pin "1") (pinfunction "1_1") (pintype "passive"))
      (node (ref "J31") (pin "01") (pinfunction "01_01") (pintype "passive"))
      (node (ref "J31") (pin "02") (pinfunction "02_02") (pintype "passive"))
      (node (ref "J32") (pin "1") (pinfunction "1_1") (pintype "passive"))
      (node (ref "J37") (pin "1") (pinfunction "1_1") (pintype "passive"))
      (node (ref "J38") (pin "1") (pinfunction "1_1") (pintype "passive"))
      (node (ref "J44") (pin "01") (pinfunction "01_01") (pintype "passive"))
      (node (ref "J44") (pin "02") (pinfunction "02_02") (pintype "passive"))
      (node (ref "J52") (pin "01") (pinfunction "01_01") (pintype "passive"))
      (node (ref "J52") (pin "02") (pinfunction "02_02") (pintype "passive"))
      (node (ref "J53") (pin "01") (pinfunction "01_01") (pintype "passive"))
      (node (ref "J53") (pin "03") (pinfunction "03_03") (pintype "passive"))
      (node (ref "J53") (pin "05") (pinfunction "05_05") (pintype "passive"))
      (node (ref "J53") (pin "07") (pinfunction "07_07") (pintype "passive"))
      (node (ref "J53") (pin "09") (pinfunction "09_09") (pintype "passive"))
      (node (ref "J53") (pin "11") (pinfunction "11_11") (pintype "passive"))
      (node (ref "J53") (pin "13") (pinfunction "13_13") (pintype "passive"))
      (node (ref "J53") (pin "15") (pinfunction "15_15") (pintype "passive"))
      (node (ref "J55") (pin "1") (pinfunction "1_1") (pintype "passive"))
      (node (ref "J56") (pin "1") (pinfunction "1_1") (pintype "passive"))
      (node (ref "P2") (pin "1") (pinfunction "1_1") (pintype "passive"))
    )
    (net (code "132") (name "Net-(P2-Pad2)") (class "Default")
      (node (ref "P2") (pin "2") (pinfunction "2_2") (pintype "passive"))
      (node (ref "R47") (pin "1") (pinfunction "1_1") (pintype "passive"))
    )
    (net (code "133") (name "Net-(P2-Pad4)") (class "Default")
      (node (ref "P2") (pin "4") (pinfunction "4_4") (pintype "passive"))
      (node (ref "R38") (pin "1") (pinfunction "1_1") (pintype "passive"))
    )
    (net (code "134") (name "Net-(P2-Pad5)") (class "Default")
      (node (ref "P2") (pin "5") (pinfunction "5_5") (pintype "passive"))
      (node (ref "R10") (pin "1") (pinfunction "1_1") (pintype "passive"))
    )
    (net (code "135") (name "Net-(P2-Pad7)") (class "Default")
      (node (ref "P2") (pin "7") (pinfunction "7_7") (pintype "passive"))
      (node (ref "R37") (pin "1") (pinfunction "1_1") (pintype "passive"))
    )
    (net (code "136") (name "unconnected-(P2-Pad3)") (class "Default")
      (node (ref "P2") (pin "3") (pinfunction "3_3") (pintype "passive+no_connect"))
    )
  )
)
